# original.net
KiCad netlist of a schematic drawn in EAGLE
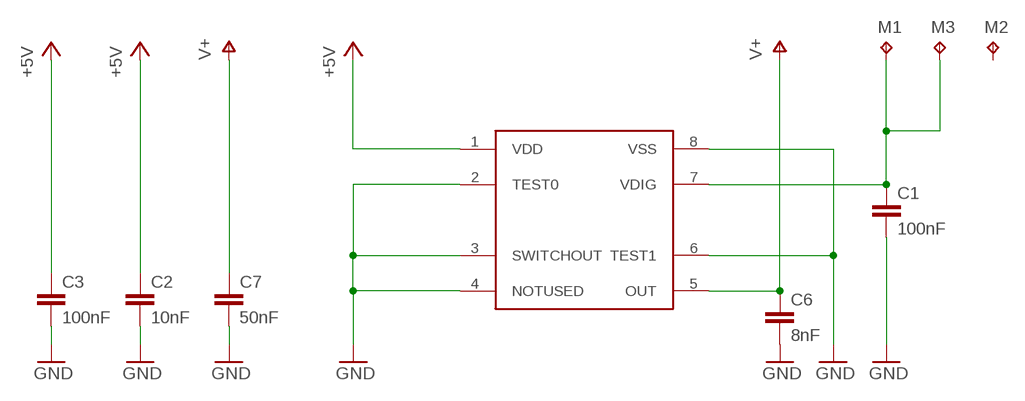
[diagram p0: schematic, sheet 1]

(export (version "E")
  (design (tool "Eeschema 10.0.6"))
  (components
    (comp (ref "C1")
      (value "100nF")
      (footprint "eagle-import:C0805K")
      (libsource (lib "eagle-import") (part "C-EUC0805K"))
    )
    (comp (ref "C2")
      (value "10nF")
      (footprint "eagle-import:C0603K")
      (libsource (lib "eagle-import") (part "C-EUC0603K"))
    )
    (comp (ref "C3")
      (value "100nF")
      (footprint "eagle-import:C0805K")
      (libsource (lib "eagle-import") (part "C-EUC0805K"))
    )
    (comp (ref "C6")
      (value "8nF")
      (footprint "eagle-import:C0603K")
      (libsource (lib "eagle-import") (part "C-EUC0603K"))
    )
    (comp (ref "C7")
      (value "50nF")
      (footprint "eagle-import:C0603K")
      (libsource (lib "eagle-import") (part "C-EUC0603K"))
    )
    (comp (ref "M1")
      (value "TPB1,27")
      (footprint "eagle-import:B1,27")
      (libsource (lib "eagle-import") (part "TPB1,27"))
    )
    (comp (ref "M2")
      (value "TPB1,27")
      (footprint "eagle-import:B1,27")
      (libsource (lib "eagle-import") (part "TPB1,27"))
    )
    (comp (ref "M3")
      (value "TPB1,27")
      (footprint "eagle-import:B1,27")
      (libsource (lib "eagle-import") (part "TPB1,27"))
    )
    (comp (ref "U$1")
      (value "MLX90316")
      (footprint "eagle-import:SO-08")
      (libsource (lib "eagle-import") (part "MLX90316"))
    )
  )
  (nets
    (net (code "1") (name "+5V") (class "Default")
      (node (ref "C2") (pin "1") (pinfunction "1_1") (pintype "passive"))
      (node (ref "C3") (pin "1") (pinfunction "1_1") (pintype "passive"))
      (node (ref "U$1") (pin "1") (pinfunction "VDD_1") (pintype "input"))
    )
    (net (code "2") (name "GND") (class "Default")
      (node (ref "C1") (pin "2") (pinfunction "2_2") (pintype "passive"))
      (node (ref "C2") (pin "2") (pinfunction "2_2") (pintype "passive"))
      (node (ref "C3") (pin "2") (pinfunction "2_2") (pintype "passive"))
      (node (ref "C6") (pin "2") (pinfunction "2_2") (pintype "passive"))
      (node (ref "C7") (pin "2") (pinfunction "2_2") (pintype "passive"))
      (node (ref "U$1") (pin "2") (pinfunction "TEST0_2") (pintype "bidirectional"))
      (node (ref "U$1") (pin "3") (pinfunction "SWITCHOUT_3") (pintype "bidirectional"))
      (node (ref "U$1") (pin "4") (pinfunction "NOTUSED_4") (pintype "bidirectional"))
      (node (ref "U$1") (pin "6") (pinfunction "TEST1_6") (pintype "bidirectional"))
      (node (ref "U$1") (pin "8") (pinfunction "VSS_8") (pintype "output"))
    )
    (net (code "3") (name "Net-(U$1-VDIG)") (class "Default")
      (node (ref "C1") (pin "1") (pinfunction "1_1") (pintype "passive"))
      (node (ref "M1") (pin "TP") (pinfunction "TP_TP") (pintype "input"))
      (node (ref "M3") (pin "TP") (pinfunction "TP_TP") (pintype "input"))
      (node (ref "U$1") (pin "7") (pinfunction "VDIG_7") (pintype "bidirectional"))
    )
    (net (code "4") (name "V+") (class "Default")
      (node (ref "C6") (pin "1") (pinfunction "1_1") (pintype "passive"))
      (node (ref "C7") (pin "1") (pinfunction "1_1") (pintype "passive"))
      (node (ref "U$1") (pin "5") (pinfunction "OUT_5") (pintype "output"))
    )
    (net (code "5") (name "unconnected-(M2-PadTP)") (class "Default")
      (node (ref "M2") (pin "TP") (pinfunction "TP_TP") (pintype "input"))
    )
  )
)
